# Limit_switch_test_circuit.net
KiCad netlist of a schematic drawn in EAGLE
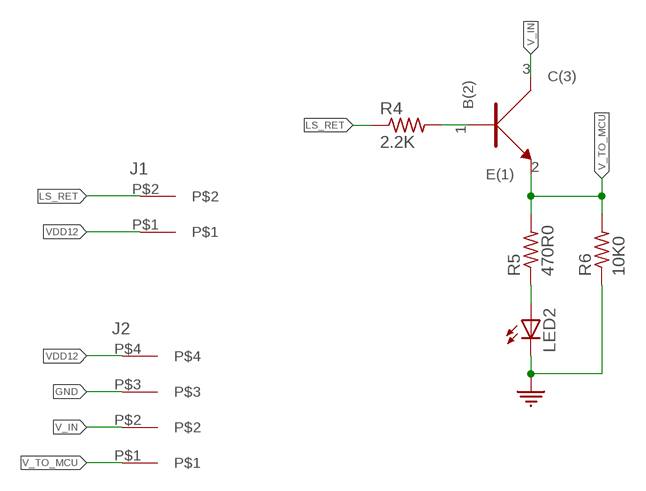
[diagram p0: schematic, sheet 1]

(export (version "E")
  (design (tool "Eeschema 10.0.6"))
  (components
    (comp (ref "J1")
      (value "2-pos")
      (footprint "eagle-import:2_3.81MM_PITCH")
      (fields (field (name "PARTNO") "691322310002"))
      (libsource (lib "eagle-import") (part "3.81MM_1_X_2_RT_ANGLE_PLUG_HEADER"))
    )
    (comp (ref "J2")
      (value "4-pos")
      (footprint "eagle-import:1X4_3.81MM_PITCH")
      (fields (field (name "PARTNO") "691322310004"))
      (libsource (lib "eagle-import") (part "3.81MM_1_X_4_RT_ANGLE_PLUG_HEADER"))
    )
    (comp (ref "LED2")
      (value "Green")
      (footprint "eagle-import:0805")
      (fields (field (name "PARTNO") "LG R971-KN-1"))
      (libsource (lib "eagle-import") (part "LED_0805_GREEN"))
    )
    (comp (ref "R4")
      (value "2.2K")
      (footprint "eagle-import:0402")
      (libsource (lib "eagle-import") (part "R_0402"))
    )
    (comp (ref "R5")
      (value "470R0")
      (footprint "eagle-import:0402")
      (fields (field (name "PARTNO") "RMCF0402JT470R"))
      (libsource (lib "eagle-import") (part "R_0402_470R0"))
    )
    (comp (ref "R6")
      (value "10K0")
      (footprint "eagle-import:0402")
      (fields (field (name "PARTNO") "RMCF0402JT10K0"))
      (libsource (lib "eagle-import") (part "R_0402_10K0"))
    )
    (comp (ref "U2")
      (value "NPN")
      (footprint "eagle-import:SOT323")
      (fields (field (name "PARTNO") "BC846BW_NPN"))
      (libsource (lib "eagle-import") (part "BC846BW"))
    )
  )
  (nets
    (net (code "1") (name "GND") (class "Default")
      (node (ref "J2") (pin "P$3") (pinfunction "P$3_P$3") (pintype "bidirectional"))
      (node (ref "LED2") (pin "2") (pinfunction "C_2") (pintype "passive"))
      (node (ref "R6") (pin "P$1") (pinfunction "1_P$1") (pintype "passive"))
    )
    (net (code "2") (name "LS_RET") (class "Default")
      (node (ref "J1") (pin "P$2") (pinfunction "P$2_P$2") (pintype "bidirectional"))
      (node (ref "R4") (pin "P$1") (pinfunction "1_P$1") (pintype "passive"))
    )
    (net (code "3") (name "Net-(LED2-A)") (class "Default")
      (node (ref "LED2") (pin "1") (pinfunction "A_1") (pintype "passive"))
      (node (ref "R5") (pin "P$1") (pinfunction "1_P$1") (pintype "passive"))
    )
    (net (code "4") (name "Net-(R4-2)") (class "Default")
      (node (ref "R4") (pin "P$2") (pinfunction "2_P$2") (pintype "passive"))
      (node (ref "U2") (pin "1") (pinfunction "B(2)_1") (pintype "input"))
    )
    (net (code "5") (name "VDD12") (class "Default")
      (node (ref "J1") (pin "P$1") (pinfunction "P$1_P$1") (pintype "bidirectional"))
      (node (ref "J2") (pin "P$4") (pinfunction "P$4_P$4") (pintype "bidirectional"))
    )
    (net (code "6") (name "V_IN") (class "Default")
      (node (ref "J2") (pin "P$2") (pinfunction "P$2_P$2") (pintype "bidirectional"))
      (node (ref "U2") (pin "3") (pinfunction "C(3)_3") (pintype "input"))
    )
    (net (code "7") (name "V_TO_MCU") (class "Default")
      (node (ref "J2") (pin "P$1") (pinfunction "P$1_P$1") (pintype "bidirectional"))
      (node (ref "R5") (pin "P$2") (pinfunction "2_P$2") (pintype "passive"))
      (node (ref "R6") (pin "P$2") (pinfunction "2_P$2") (pintype "passive"))
      (node (ref "U2") (pin "2") (pinfunction "E(1)_2") (pintype "output"))
    )
  )
)
